# Parallel_CS_V5_repeated.net
KiCad netlist of a schematic drawn in EAGLE
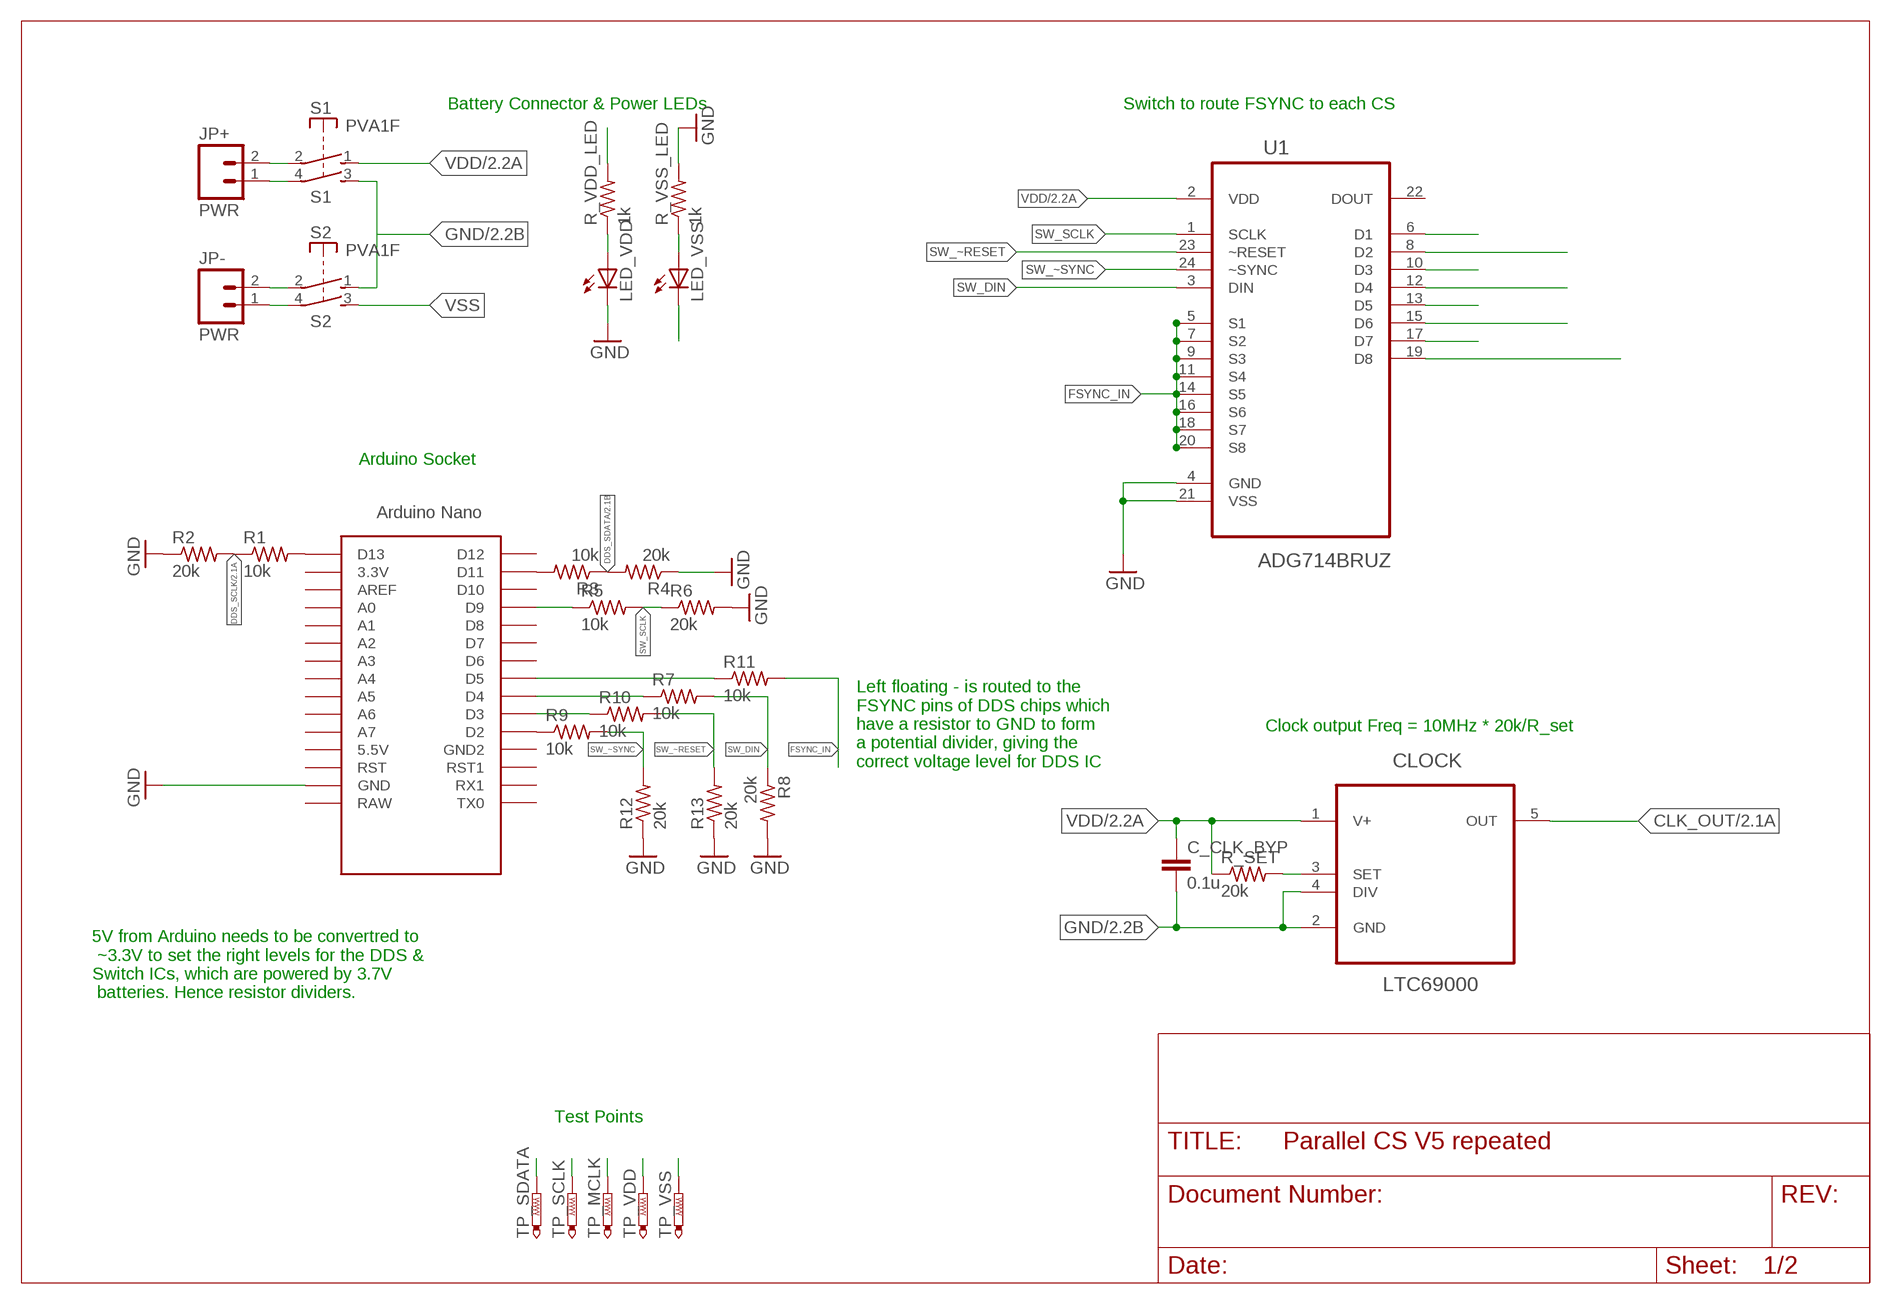
[diagram p0: schematic, sheet 1]
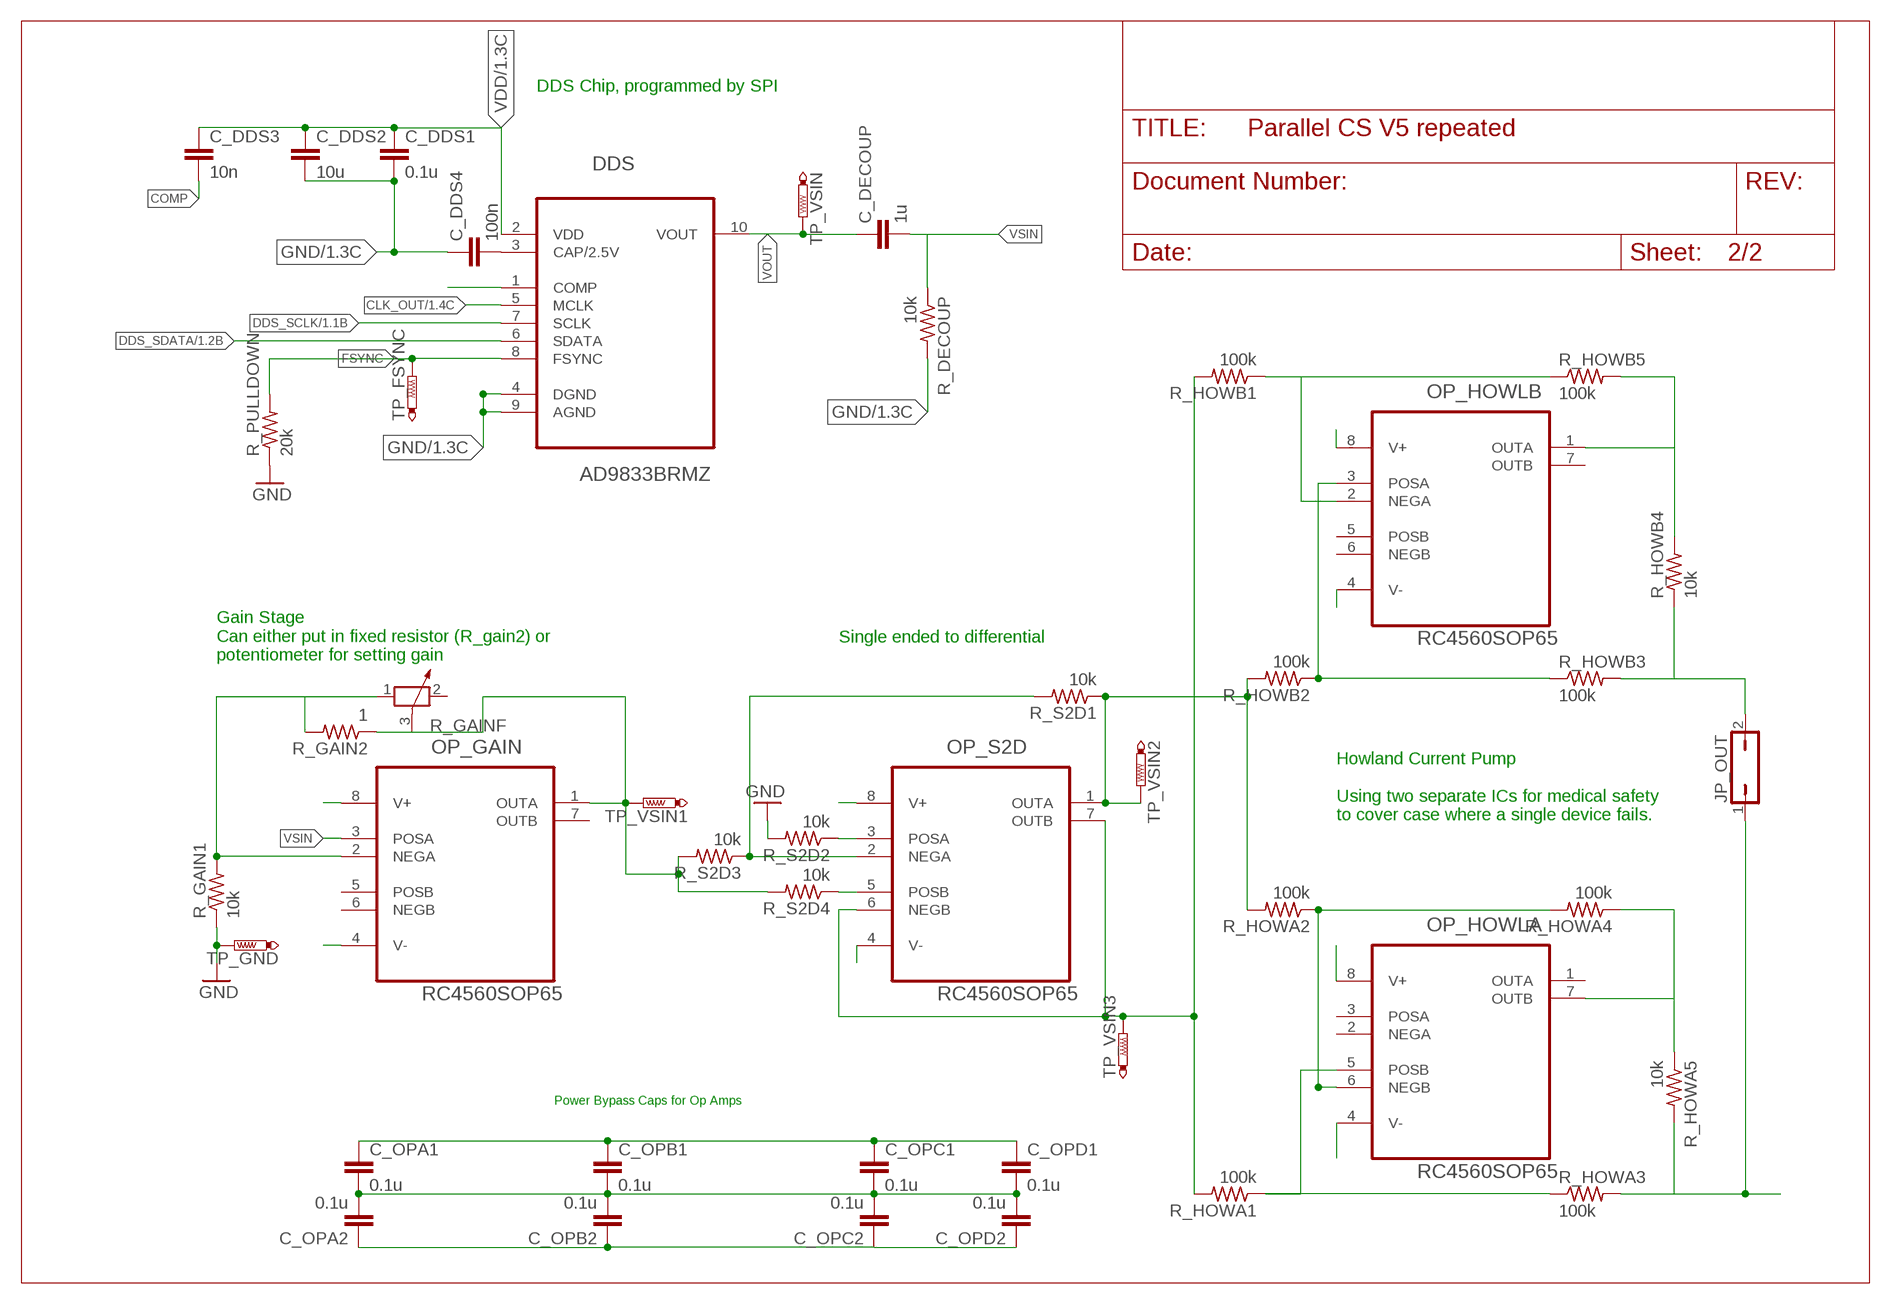
[diagram p1: schematic, sheet 2]

(export (version "E")
  (design (tool "Eeschema 10.0.6"))
  (components
    (comp (ref "CLOCK")
      (value "LTC69000")
      (footprint "eagle-import:SOT23-5L")
      (libsource (lib "eagle-import") (part "LTC69000"))
    )
    (comp (ref "C_CLK_BYP")
      (value "0.1u")
      (footprint "eagle-import:C0805")
      (libsource (lib "eagle-import") (part "C-EUC0805"))
    )
    (comp (ref "JP+")
      (value "PWR")
      (footprint "eagle-import:JST-2-SMD")
      (libsource (lib "eagle-import") (part "M02-JST-2MM-SMT"))
    )
    (comp (ref "JP-")
      (value "PWR")
      (footprint "eagle-import:JST-2-SMD")
      (libsource (lib "eagle-import") (part "M02-JST-2MM-SMT"))
    )
    (comp (ref "LED_VDD")
      (value "LEDSML0805")
      (footprint "eagle-import:SML0805")
      (libsource (lib "eagle-import") (part "LEDSML0805"))
    )
    (comp (ref "LED_VSS")
      (value "LEDSML0805")
      (footprint "eagle-import:SML0805")
      (libsource (lib "eagle-import") (part "LEDSML0805"))
    )
    (comp (ref "R1")
      (value "10k")
      (footprint "eagle-import:R0805")
      (libsource (lib "eagle-import") (part "resistor_R-US_R0805"))
    )
    (comp (ref "R2")
      (value "20k")
      (footprint "eagle-import:R0805")
      (libsource (lib "eagle-import") (part "resistor_R-US_R0805"))
    )
    (comp (ref "R3")
      (value "10k")
      (footprint "eagle-import:R0805")
      (libsource (lib "eagle-import") (part "resistor_R-US_R0805"))
    )
    (comp (ref "R4")
      (value "20k")
      (footprint "eagle-import:R0805")
      (libsource (lib "eagle-import") (part "resistor_R-US_R0805"))
    )
    (comp (ref "R5")
      (value "10k")
      (footprint "eagle-import:R0805")
      (libsource (lib "eagle-import") (part "resistor_R-US_R0805"))
    )
    (comp (ref "R6")
      (value "20k")
      (footprint "eagle-import:R0805")
      (libsource (lib "eagle-import") (part "resistor_R-US_R0805"))
    )
    (comp (ref "R7")
      (value "10k")
      (footprint "eagle-import:R0805")
      (libsource (lib "eagle-import") (part "resistor_R-US_R0805"))
    )
    (comp (ref "R8")
      (value "20k")
      (footprint "eagle-import:R0805")
      (libsource (lib "eagle-import") (part "resistor_R-US_R0805"))
    )
    (comp (ref "R9")
      (value "10k")
      (footprint "eagle-import:R0805")
      (libsource (lib "eagle-import") (part "resistor_R-US_R0805"))
    )
    (comp (ref "R10")
      (value "10k")
      (footprint "eagle-import:R0805")
      (libsource (lib "eagle-import") (part "resistor_R-US_R0805"))
    )
    (comp (ref "R11")
      (value "10k")
      (footprint "eagle-import:R0805")
      (libsource (lib "eagle-import") (part "resistor_R-US_R0805"))
    )
    (comp (ref "R12")
      (value "20k")
      (footprint "eagle-import:R0805")
      (libsource (lib "eagle-import") (part "resistor_R-US_R0805"))
    )
    (comp (ref "R13")
      (value "20k")
      (footprint "eagle-import:R0805")
      (libsource (lib "eagle-import") (part "resistor_R-US_R0805"))
    )
    (comp (ref "R_SET")
      (value "20k")
      (footprint "eagle-import:R0805")
      (libsource (lib "eagle-import") (part "resistor_R-US_R0805"))
    )
    (comp (ref "R_VDD_LED")
      (value "1k")
      (footprint "eagle-import:M0805")
      (libsource (lib "eagle-import") (part "resistor_R-US_M0805"))
    )
    (comp (ref "R_VSS_LED")
      (value "1k")
      (footprint "eagle-import:M0805")
      (libsource (lib "eagle-import") (part "resistor_R-US_M0805"))
    )
    (comp (ref "S1")
      (value "PVA1F")
      (footprint "eagle-import:PVA1F")
      (libsource (lib "eagle-import") (part "PVA1F"))
    )
    (comp (ref "S2")
      (value "PVA1F")
      (footprint "eagle-import:PVA1F")
      (libsource (lib "eagle-import") (part "PVA1F"))
    )
    (comp (ref "TP_MCLK")
      (value "PTR1PAD1-13")
      (footprint "eagle-import:P1-13")
      (libsource (lib "eagle-import") (part "PTR1PAD1-13"))
    )
    (comp (ref "TP_SCLK")
      (value "PTR1PAD1-13")
      (footprint "eagle-import:P1-13")
      (libsource (lib "eagle-import") (part "PTR1PAD1-13"))
    )
    (comp (ref "TP_SDATA")
      (value "PTR1PAD1-13")
      (footprint "eagle-import:P1-13")
      (libsource (lib "eagle-import") (part "PTR1PAD1-13"))
    )
    (comp (ref "TP_VDD")
      (value "PTR1PAD1-13")
      (footprint "eagle-import:P1-13")
      (libsource (lib "eagle-import") (part "PTR1PAD1-13"))
    )
    (comp (ref "TP_VSS")
      (value "PTR1PAD1-13")
      (footprint "eagle-import:P1-13")
      (libsource (lib "eagle-import") (part "PTR1PAD1-13"))
    )
    (comp (ref "U$1")
      (value "NANO")
      (footprint "eagle-import:NANO")
      (libsource (lib "eagle-import") (part "NANO"))
    )
    (comp (ref "U1")
      (value "ADG714BRUZ")
      (footprint "eagle-import:SOP65P640X120-24N")
      (libsource (lib "eagle-import") (part "ADG714BRUZ"))
    )
    (comp (ref "C_DDS1")
      (value "0.1u")
      (footprint "eagle-import:C0805")
      (libsource (lib "eagle-import") (part "C-EUC0805"))
    )
    (comp (ref "C_DDS2")
      (value "10u")
      (footprint "eagle-import:C0805")
      (libsource (lib "eagle-import") (part "C-EUC0805"))
    )
    (comp (ref "C_DDS3")
      (value "10n")
      (footprint "eagle-import:C0805")
      (libsource (lib "eagle-import") (part "C-EUC0805"))
    )
    (comp (ref "C_DDS4")
      (value "100n")
      (footprint "eagle-import:C0805")
      (libsource (lib "eagle-import") (part "C-EUC0805"))
    )
    (comp (ref "C_DECOUP")
      (value "1u")
      (footprint "eagle-import:C0805")
      (libsource (lib "eagle-import") (part "C-EUC0805"))
    )
    (comp (ref "C_OPA1")
      (value "0.1u")
      (footprint "eagle-import:C0805")
      (libsource (lib "eagle-import") (part "C-EUC0805"))
    )
    (comp (ref "C_OPA2")
      (value "0.1u")
      (footprint "eagle-import:C0805")
      (libsource (lib "eagle-import") (part "C-EUC0805"))
    )
    (comp (ref "C_OPB1")
      (value "0.1u")
      (footprint "eagle-import:C0805")
      (libsource (lib "eagle-import") (part "C-EUC0805"))
    )
    (comp (ref "C_OPB2")
      (value "0.1u")
      (footprint "eagle-import:C0805")
      (libsource (lib "eagle-import") (part "C-EUC0805"))
    )
    (comp (ref "C_OPC1")
      (value "0.1u")
      (footprint "eagle-import:C0805")
      (libsource (lib "eagle-import") (part "C-EUC0805"))
    )
    (comp (ref "C_OPC2")
      (value "0.1u")
      (footprint "eagle-import:C0805")
      (libsource (lib "eagle-import") (part "C-EUC0805"))
    )
    (comp (ref "C_OPD1")
      (value "0.1u")
      (footprint "eagle-import:C0805")
      (libsource (lib "eagle-import") (part "C-EUC0805"))
    )
    (comp (ref "C_OPD2")
      (value "0.1u")
      (footprint "eagle-import:C0805")
      (libsource (lib "eagle-import") (part "C-EUC0805"))
    )
    (comp (ref "DDS")
      (value "AD9833BRMZ")
      (footprint "eagle-import:SOP50P490X110-10N")
      (libsource (lib "eagle-import") (part "AD9833BRMZ"))
    )
    (comp (ref "JP_OUT")
      (value "JP1Q")
      (footprint "eagle-import:JP1")
      (libsource (lib "eagle-import") (part "JP1Q"))
    )
    (comp (ref "OP_GAIN")
      (value "RC4560SOP65")
      (footprint "eagle-import:SOP65P490X109-8N")
      (libsource (lib "eagle-import") (part "RC4560SOP65"))
    )
    (comp (ref "OP_HOWLA")
      (value "RC4560SOP65")
      (footprint "eagle-import:SOP65P490X109-8N")
      (libsource (lib "eagle-import") (part "RC4560SOP65"))
    )
    (comp (ref "OP_HOWLB")
      (value "RC4560SOP65")
      (footprint "eagle-import:SOP65P490X109-8N")
      (libsource (lib "eagle-import") (part "RC4560SOP65"))
    )
    (comp (ref "OP_S2D")
      (value "RC4560SOP65")
      (footprint "eagle-import:SOP65P490X109-8N")
      (libsource (lib "eagle-import") (part "RC4560SOP65"))
    )
    (comp (ref "R_DECOUP")
      (value "10k")
      (footprint "eagle-import:R0805")
      (libsource (lib "eagle-import") (part "R-US_R0805"))
    )
    (comp (ref "R_GAIN1")
      (value "10k")
      (footprint "eagle-import:R0805")
      (libsource (lib "eagle-import") (part "R-US_R0805"))
    )
    (comp (ref "R_GAIN2")
      (value "1")
      (footprint "eagle-import:R0805")
      (libsource (lib "eagle-import") (part "R-US_R0805"))
    )
    (comp (ref "R_GAINF")
      (value "POTENTIOMETER_PT-10")
      (footprint "eagle-import:PT-10")
      (libsource (lib "eagle-import") (part "POTENTIOMETER_PT-10"))
    )
    (comp (ref "R_HOWA1")
      (value "100k")
      (footprint "eagle-import:R0805")
      (libsource (lib "eagle-import") (part "R-US_R0805"))
    )
    (comp (ref "R_HOWA2")
      (value "100k")
      (footprint "eagle-import:R0805")
      (libsource (lib "eagle-import") (part "R-US_R0805"))
    )
    (comp (ref "R_HOWA3")
      (value "100k")
      (footprint "eagle-import:R0805")
      (libsource (lib "eagle-import") (part "R-US_R0805"))
    )
    (comp (ref "R_HOWA4")
      (value "100k")
      (footprint "eagle-import:R0805")
      (libsource (lib "eagle-import") (part "R-US_R0805"))
    )
    (comp (ref "R_HOWA5")
      (value "10k")
      (footprint "eagle-import:R0805")
      (libsource (lib "eagle-import") (part "R-US_R0805"))
    )
    (comp (ref "R_HOWB1")
      (value "100k")
      (footprint "eagle-import:R0805")
      (libsource (lib "eagle-import") (part "R-US_R0805"))
    )
    (comp (ref "R_HOWB2")
      (value "100k")
      (footprint "eagle-import:R0805")
      (libsource (lib "eagle-import") (part "R-US_R0805"))
    )
    (comp (ref "R_HOWB3")
      (value "100k")
      (footprint "eagle-import:R0805")
      (libsource (lib "eagle-import") (part "R-US_R0805"))
    )
    (comp (ref "R_HOWB4")
      (value "10k")
      (footprint "eagle-import:R0805")
      (libsource (lib "eagle-import") (part "R-US_R0805"))
    )
    (comp (ref "R_HOWB5")
      (value "100k")
      (footprint "eagle-import:R0805")
      (libsource (lib "eagle-import") (part "R-US_R0805"))
    )
    (comp (ref "R_PULLDOWN")
      (value "20k")
      (footprint "eagle-import:R0805")
      (libsource (lib "eagle-import") (part "R-US_R0805"))
    )
    (comp (ref "R_S2D1")
      (value "10k")
      (footprint "eagle-import:R0805")
      (libsource (lib "eagle-import") (part "R-US_R0805"))
    )
    (comp (ref "R_S2D2")
      (value "10k")
      (footprint "eagle-import:R0805")
      (libsource (lib "eagle-import") (part "R-US_R0805"))
    )
    (comp (ref "R_S2D3")
      (value "10k")
      (footprint "eagle-import:R0805")
      (libsource (lib "eagle-import") (part "R-US_R0805"))
    )
    (comp (ref "R_S2D4")
      (value "10k")
      (footprint "eagle-import:R0805")
      (libsource (lib "eagle-import") (part "R-US_R0805"))
    )
    (comp (ref "TP_FSYNC")
      (value "PTR1PAD1-13")
      (footprint "eagle-import:P1-13")
      (libsource (lib "eagle-import") (part "PTR1PAD1-13"))
    )
    (comp (ref "TP_GND")
      (value "PTR1PAD1-13")
      (footprint "eagle-import:P1-13")
      (libsource (lib "eagle-import") (part "PTR1PAD1-13"))
    )
    (comp (ref "TP_VSIN")
      (value "PTR1PAD1-13")
      (footprint "eagle-import:P1-13")
      (libsource (lib "eagle-import") (part "PTR1PAD1-13"))
    )
    (comp (ref "TP_VSIN1")
      (value "PTR1PAD1-13")
      (footprint "eagle-import:P1-13")
      (libsource (lib "eagle-import") (part "PTR1PAD1-13"))
    )
    (comp (ref "TP_VSIN2")
      (value "PTR1PAD1-13")
      (footprint "eagle-import:P1-13")
      (libsource (lib "eagle-import") (part "PTR1PAD1-13"))
    )
    (comp (ref "TP_VSIN3")
      (value "PTR1PAD1-13")
      (footprint "eagle-import:P1-13")
      (libsource (lib "eagle-import") (part "PTR1PAD1-13"))
    )
  )
  (nets
    (net (code "1") (name "CLK_OUT") (class "Default")
      (node (ref "CLOCK") (pin "5") (pinfunction "OUT_5") (pintype "output"))
      (node (ref "DDS") (pin "5") (pinfunction "MCLK_5") (pintype "input"))
      (node (ref "TP_MCLK") (pin "TP") (pinfunction "TP_TP") (pintype "input"))
    )
    (net (code "2") (name "COMP") (class "Default")
      (node (ref "C_DDS3") (pin "2") (pinfunction "2_2") (pintype "passive"))
      (node (ref "DDS") (pin "1") (pinfunction "COMP_1") (pintype "passive"))
    )
    (net (code "3") (name "DDS_SCLK") (class "Default")
      (node (ref "DDS") (pin "7") (pinfunction "SCLK_7") (pintype "input"))
      (node (ref "R1") (pin "1") (pinfunction "1_1") (pintype "passive"))
      (node (ref "R2") (pin "2") (pinfunction "2_2") (pintype "passive"))
      (node (ref "TP_SCLK") (pin "TP") (pinfunction "TP_TP") (pintype "input"))
    )
    (net (code "4") (name "DDS_SDATA") (class "Default")
      (node (ref "DDS") (pin "6") (pinfunction "SDATA_6") (pintype "input"))
      (node (ref "R3") (pin "1") (pinfunction "1_1") (pintype "passive"))
      (node (ref "R4") (pin "2") (pinfunction "2_2") (pintype "passive"))
      (node (ref "TP_SDATA") (pin "TP") (pinfunction "TP_TP") (pintype "input"))
    )
    (net (code "5") (name "FSYNC") (class "Default")
      (node (ref "DDS") (pin "8") (pinfunction "FSYNC_8") (pintype "input"))
      (node (ref "R_PULLDOWN") (pin "2") (pinfunction "2_2") (pintype "passive"))
      (node (ref "TP_FSYNC") (pin "TP") (pinfunction "TP_TP") (pintype "input"))
    )
    (net (code "6") (name "FSYNC_IN") (class "Default")
      (node (ref "R11") (pin "2") (pinfunction "2_2") (pintype "passive"))
      (node (ref "U1") (pin "11") (pinfunction "S4_11") (pintype "bidirectional"))
      (node (ref "U1") (pin "14") (pinfunction "S5_14") (pintype "bidirectional"))
      (node (ref "U1") (pin "16") (pinfunction "S6_16") (pintype "bidirectional"))
      (node (ref "U1") (pin "18") (pinfunction "S7_18") (pintype "bidirectional"))
      (node (ref "U1") (pin "20") (pinfunction "S8_20") (pintype "bidirectional"))
      (node (ref "U1") (pin "5") (pinfunction "S1_5") (pintype "bidirectional"))
      (node (ref "U1") (pin "7") (pinfunction "S2_7") (pintype "bidirectional"))
      (node (ref "U1") (pin "9") (pinfunction "S3_9") (pintype "bidirectional"))
    )
    (net (code "7") (name "GND") (class "Default")
      (node (ref "CLOCK") (pin "2") (pinfunction "GND_2") (pintype "passive"))
      (node (ref "CLOCK") (pin "4") (pinfunction "DIV_4") (pintype "input"))
      (node (ref "C_CLK_BYP") (pin "2") (pinfunction "2_2") (pintype "passive"))
      (node (ref "C_DDS1") (pin "2") (pinfunction "2_2") (pintype "passive"))
      (node (ref "C_DDS2") (pin "2") (pinfunction "2_2") (pintype "passive"))
      (node (ref "C_DDS4") (pin "1") (pinfunction "1_1") (pintype "passive"))
      (node (ref "C_OPA1") (pin "2") (pinfunction "2_2") (pintype "passive"))
      (node (ref "C_OPA2") (pin "2") (pinfunction "2_2") (pintype "passive"))
      (node (ref "C_OPB1") (pin "2") (pinfunction "2_2") (pintype "passive"))
      (node (ref "C_OPB2") (pin "2") (pinfunction "2_2") (pintype "passive"))
      (node (ref "C_OPC1") (pin "2") (pinfunction "2_2") (pintype "passive"))
      (node (ref "C_OPC2") (pin "2") (pinfunction "2_2") (pintype "passive"))
      (node (ref "C_OPD1") (pin "2") (pinfunction "2_2") (pintype "passive"))
      (node (ref "C_OPD2") (pin "2") (pinfunction "2_2") (pintype "passive"))
      (node (ref "DDS") (pin "4") (pinfunction "DGND_4") (pintype "passive"))
      (node (ref "DDS") (pin "9") (pinfunction "AGND_9") (pintype "passive"))
      (node (ref "LED_VDD") (pin "C") (pinfunction "C_C") (pintype "passive"))
      (node (ref "R12") (pin "1") (pinfunction "1_1") (pintype "passive"))
      (node (ref "R13") (pin "1") (pinfunction "1_1") (pintype "passive"))
      (node (ref "R2") (pin "1") (pinfunction "1_1") (pintype "passive"))
      (node (ref "R4") (pin "1") (pinfunction "1_1") (pintype "passive"))
      (node (ref "R6") (pin "2") (pinfunction "2_2") (pintype "passive"))
      (node (ref "R8") (pin "2") (pinfunction "2_2") (pintype "passive"))
      (node (ref "R_DECOUP") (pin "2") (pinfunction "2_2") (pintype "passive"))
      (node (ref "R_GAIN1") (pin "1") (pinfunction "1_1") (pintype "passive"))
      (node (ref "R_PULLDOWN") (pin "1") (pinfunction "1_1") (pintype "passive"))
      (node (ref "R_S2D2") (pin "2") (pinfunction "2_2") (pintype "passive"))
      (node (ref "R_VSS_LED") (pin "2") (pinfunction "2_2") (pintype "passive"))
      (node (ref "S1") (pin "3") (pinfunction "S_3") (pintype "passive"))
      (node (ref "S2") (pin "1") (pinfunction "S_1") (pintype "passive"))
      (node (ref "TP_GND") (pin "TP") (pinfunction "TP_TP") (pintype "input"))
      (node (ref "U$1") (pin "GND") (pinfunction "GND_GND") (pintype "bidirectional"))
      (node (ref "U1") (pin "21") (pinfunction "VSS_21") (pintype "power_in"))
      (node (ref "U1") (pin "4") (pinfunction "GND_4") (pintype "passive"))
    )
    (net (code "8") (name "Net-(CLOCK-SET)") (class "Default")
      (node (ref "CLOCK") (pin "3") (pinfunction "SET_3") (pintype "input"))
      (node (ref "R_SET") (pin "2") (pinfunction "2_2") (pintype "passive"))
    )
    (net (code "9") (name "Net-(DDS-CAP{slash}2.5V)") (class "Default")
      (node (ref "C_DDS4") (pin "2") (pinfunction "2_2") (pintype "passive"))
      (node (ref "DDS") (pin "3") (pinfunction "CAP/2.5V_3") (pintype "passive"))
    )
    (net (code "10") (name "Net-(JP_OUT-Pad1)") (class "Default")
      (node (ref "JP_OUT") (pin "1") (pinfunction "1_1") (pintype "passive"))
      (node (ref "R_HOWA3") (pin "2") (pinfunction "2_2") (pintype "passive"))
      (node (ref "R_HOWA5") (pin "2") (pinfunction "2_2") (pintype "passive"))
    )
    (net (code "11") (name "Net-(JP_OUT-Pad2)") (class "Default")
      (node (ref "JP_OUT") (pin "2") (pinfunction "2_2") (pintype "passive"))
      (node (ref "R_HOWB3") (pin "2") (pinfunction "2_2") (pintype "passive"))
      (node (ref "R_HOWB4") (pin "1") (pinfunction "1_1") (pintype "passive"))
    )
    (net (code "12") (name "Net-(LED_VDD-PadA)") (class "Default")
      (node (ref "LED_VDD") (pin "A") (pinfunction "A_A") (pintype "passive"))
      (node (ref "R_VDD_LED") (pin "1") (pinfunction "1_1") (pintype "passive"))
    )
    (net (code "13") (name "Net-(LED_VSS-PadA)") (class "Default")
      (node (ref "LED_VSS") (pin "A") (pinfunction "A_A") (pintype "passive"))
      (node (ref "R_VSS_LED") (pin "1") (pinfunction "1_1") (pintype "passive"))
    )
    (net (code "14") (name "Net-(OP_GAIN-NEGA)") (class "Default")
      (node (ref "OP_GAIN") (pin "2") (pinfunction "NEGA_2") (pintype "input"))
      (node (ref "R_GAIN1") (pin "2") (pinfunction "2_2") (pintype "passive"))
      (node (ref "R_GAIN2") (pin "2") (pinfunction "2_2") (pintype "passive"))
      (node (ref "R_GAINF") (pin "1") (pinfunction "1_1") (pintype "passive"))
    )
    (net (code "15") (name "Net-(OP_GAIN-OUTA)") (class "Default")
      (node (ref "OP_GAIN") (pin "1") (pinfunction "OUTA_1") (pintype "output"))
      (node (ref "R_GAIN2") (pin "1") (pinfunction "1_1") (pintype "passive"))
      (node (ref "R_GAINF") (pin "3") (pinfunction "3_3") (pintype "passive"))
      (node (ref "R_S2D3") (pin "2") (pinfunction "2_2") (pintype "passive"))
      (node (ref "R_S2D4") (pin "2") (pinfunction "2_2") (pintype "passive"))
      (node (ref "TP_VSIN1") (pin "TP") (pinfunction "TP_TP") (pintype "input"))
    )
    (net (code "16") (name "Net-(OP_HOWLA-NEGB)") (class "Default")
      (node (ref "OP_HOWLA") (pin "6") (pinfunction "NEGB_6") (pintype "input"))
      (node (ref "R_HOWA2") (pin "1") (pinfunction "1_1") (pintype "passive"))
      (node (ref "R_HOWA4") (pin "2") (pinfunction "2_2") (pintype "passive"))
    )
    (net (code "17") (name "Net-(OP_HOWLA-OUTB)") (class "Default")
      (node (ref "OP_HOWLA") (pin "7") (pinfunction "OUTB_7") (pintype "output"))
      (node (ref "R_HOWA4") (pin "1") (pinfunction "1_1") (pintype "passive"))
      (node (ref "R_HOWA5") (pin "1") (pinfunction "1_1") (pintype "passive"))
    )
    (net (code "18") (name "Net-(OP_HOWLA-POSB)") (class "Default")
      (node (ref "OP_HOWLA") (pin "5") (pinfunction "POSB_5") (pintype "input"))
      (node (ref "R_HOWA1") (pin "1") (pinfunction "1_1") (pintype "passive"))
      (node (ref "R_HOWA3") (pin "1") (pinfunction "1_1") (pintype "passive"))
    )
    (net (code "19") (name "Net-(OP_HOWLB-NEGA)") (class "Default")
      (node (ref "OP_HOWLB") (pin "2") (pinfunction "NEGA_2") (pintype "input"))
      (node (ref "R_HOWB1") (pin "1") (pinfunction "1_1") (pintype "passive"))
      (node (ref "R_HOWB5") (pin "1") (pinfunction "1_1") (pintype "passive"))
    )
    (net (code "20") (name "Net-(OP_HOWLB-OUTA)") (class "Default")
      (node (ref "OP_HOWLB") (pin "1") (pinfunction "OUTA_1") (pintype "output"))
      (node (ref "R_HOWB4") (pin "2") (pinfunction "2_2") (pintype "passive"))
      (node (ref "R_HOWB5") (pin "2") (pinfunction "2_2") (pintype "passive"))
    )
    (net (code "21") (name "Net-(OP_HOWLB-POSA)") (class "Default")
      (node (ref "OP_HOWLB") (pin "3") (pinfunction "POSA_3") (pintype "input"))
      (node (ref "R_HOWB2") (pin "1") (pinfunction "1_1") (pintype "passive"))
      (node (ref "R_HOWB3") (pin "1") (pinfunction "1_1") (pintype "passive"))
    )
    (net (code "22") (name "Net-(OP_S2D-NEGA)") (class "Default")
      (node (ref "OP_S2D") (pin "2") (pinfunction "NEGA_2") (pintype "input"))
      (node (ref "R_S2D1") (pin "2") (pinfunction "2_2") (pintype "passive"))
      (node (ref "R_S2D3") (pin "1") (pinfunction "1_1") (pintype "passive"))
    )
    (net (code "23") (name "Net-(OP_S2D-NEGB)") (class "Default")
      (node (ref "OP_S2D") (pin "6") (pinfunction "NEGB_6") (pintype "input"))
      (node (ref "OP_S2D") (pin "7") (pinfunction "OUTB_7") (pintype "output"))
      (node (ref "R_HOWA1") (pin "2") (pinfunction "2_2") (pintype "passive"))
      (node (ref "R_HOWB1") (pin "2") (pinfunction "2_2") (pintype "passive"))
      (node (ref "TP_VSIN3") (pin "TP") (pinfunction "TP_TP") (pintype "input"))
    )
    (net (code "24") (name "Net-(OP_S2D-OUTA)") (class "Default")
      (node (ref "OP_S2D") (pin "1") (pinfunction "OUTA_1") (pintype "output"))
      (node (ref "R_HOWA2") (pin "2") (pinfunction "2_2") (pintype "passive"))
      (node (ref "R_HOWB2") (pin "2") (pinfunction "2_2") (pintype "passive"))
      (node (ref "R_S2D1") (pin "1") (pinfunction "1_1") (pintype "passive"))
      (node (ref "TP_VSIN2") (pin "TP") (pinfunction "TP_TP") (pintype "input"))
    )
    (net (code "25") (name "Net-(OP_S2D-POSA)") (class "Default")
      (node (ref "OP_S2D") (pin "3") (pinfunction "POSA_3") (pintype "input"))
      (node (ref "R_S2D2") (pin "1") (pinfunction "1_1") (pintype "passive"))
    )
    (net (code "26") (name "Net-(OP_S2D-POSB)") (class "Default")
      (node (ref "OP_S2D") (pin "5") (pinfunction "POSB_5") (pintype "input"))
      (node (ref "R_S2D4") (pin "1") (pinfunction "1_1") (pintype "passive"))
    )
    (net (code "27") (name "Net-(R1-Pad2)") (class "Default")
      (node (ref "R1") (pin "2") (pinfunction "2_2") (pintype "passive"))
      (node (ref "U$1") (pin "D13") (pinfunction "D13_D13") (pintype "bidirectional"))
    )
    (net (code "28") (name "Net-(R3-Pad2)") (class "Default")
      (node (ref "R3") (pin "2") (pinfunction "2_2") (pintype "passive"))
      (node (ref "U$1") (pin "D11") (pinfunction "D11_D11") (pintype "bidirectional"))
    )
    (net (code "29") (name "Net-(R5-Pad1)") (class "Default")
      (node (ref "R5") (pin "1") (pinfunction "1_1") (pintype "passive"))
      (node (ref "U$1") (pin "D9") (pinfunction "D9_D9") (pintype "bidirectional"))
    )
    (net (code "30") (name "Net-(R7-Pad1)") (class "Default")
      (node (ref "R7") (pin "1") (pinfunction "1_1") (pintype "passive"))
      (node (ref "U$1") (pin "D4") (pinfunction "D4_D4") (pintype "bidirectional"))
    )
    (net (code "31") (name "Net-(R9-Pad1)") (class "Default")
      (node (ref "R9") (pin "1") (pinfunction "1_1") (pintype "passive"))
      (node (ref "U$1") (pin "D2") (pinfunction "D2_D2") (pintype "bidirectional"))
    )
    (net (code "32") (name "Net-(R10-Pad1)") (class "Default")
      (node (ref "R10") (pin "1") (pinfunction "1_1") (pintype "passive"))
      (node (ref "U$1") (pin "D3") (pinfunction "D3_D3") (pintype "bidirectional"))
    )
    (net (code "33") (name "Net-(R11-Pad1)") (class "Default")
      (node (ref "R11") (pin "1") (pinfunction "1_1") (pintype "passive"))
      (node (ref "U$1") (pin "D5") (pinfunction "D5_D5") (pintype "bidirectional"))
    )
    (net (code "34") (name "Net-(S1A-P)") (class "Default")
      (node (ref "JP+") (pin "2") (pinfunction "2_2") (pintype "passive"))
      (node (ref "S1") (pin "2") (pinfunction "P_2") (pintype "passive"))
    )
    (net (code "35") (name "Net-(S1B-P)") (class "Default")
      (node (ref "JP+") (pin "1") (pinfunction "1_1") (pintype "passive"))
      (node (ref "S1") (pin "4") (pinfunction "P_4") (pintype "passive"))
    )
    (net (code "36") (name "Net-(S2A-P)") (class "Default")
      (node (ref "JP-") (pin "2") (pinfunction "2_2") (pintype "passive"))
      (node (ref "S2") (pin "2") (pinfunction "P_2") (pintype "passive"))
    )
    (net (code "37") (name "Net-(S2B-P)") (class "Default")
      (node (ref "JP-") (pin "1") (pinfunction "1_1") (pintype "passive"))
      (node (ref "S2") (pin "4") (pinfunction "P_4") (pintype "passive"))
    )
    (net (code "38") (name "SW_DIN") (class "Default")
      (node (ref "R7") (pin "2") (pinfunction "2_2") (pintype "passive"))
      (node (ref "R8") (pin "1") (pinfunction "1_1") (pintype "passive"))
      (node (ref "U1") (pin "3") (pinfunction "DIN_3") (pintype "input"))
    )
    (net (code "39") (name "SW_SCLK") (class "Default")
      (node (ref "R5") (pin "2") (pinfunction "2_2") (pintype "passive"))
      (node (ref "R6") (pin "1") (pinfunction "1_1") (pintype "passive"))
      (node (ref "U1") (pin "1") (pinfunction "SCLK_1") (pintype "input"))
    )
    (net (code "40") (name "SW_~{RESET}") (class "Default")
      (node (ref "R10") (pin "2") (pinfunction "2_2") (pintype "passive"))
      (node (ref "R13") (pin "2") (pinfunction "2_2") (pintype "passive"))
      (node (ref "U1") (pin "23") (pinfunction "~{RESET}_23") (pintype "input"))
    )
    (net (code "41") (name "SW_~{SYNC}") (class "Default")
      (node (ref "R12") (pin "2") (pinfunction "2_2") (pintype "passive"))
      (node (ref "R9") (pin "2") (pinfunction "2_2") (pintype "passive"))
      (node (ref "U1") (pin "24") (pinfunction "~{SYNC}_24") (pintype "input"))
    )
    (net (code "42") (name "VDD") (class "Default")
      (node (ref "CLOCK") (pin "1") (pinfunction "V+_1") (pintype "power_in"))
      (node (ref "C_CLK_BYP") (pin "1") (pinfunction "1_1") (pintype "passive"))
      (node (ref "C_DDS1") (pin "1") (pinfunction "1_1") (pintype "passive"))
      (node (ref "C_DDS2") (pin "1") (pinfunction "1_1") (pintype "passive"))
      (node (ref "C_DDS3") (pin "1") (pinfunction "1_1") (pintype "passive"))
      (node (ref "C_OPA1") (pin "1") (pinfunction "1_1") (pintype "passive"))
      (node (ref "C_OPB1") (pin "1") (pinfunction "1_1") (pintype "passive"))
      (node (ref "C_OPC1") (pin "1") (pinfunction "1_1") (pintype "passive"))
      (node (ref "C_OPD1") (pin "1") (pinfunction "1_1") (pintype "passive"))
      (node (ref "DDS") (pin "2") (pinfunction "VDD_2") (pintype "power_in"))
      (node (ref "OP_GAIN") (pin "8") (pinfunction "V+_8") (pintype "power_in"))
      (node (ref "OP_HOWLA") (pin "8") (pinfunction "V+_8") (pintype "power_in"))
      (node (ref "OP_HOWLB") (pin "8") (pinfunction "V+_8") (pintype "power_in"))
      (node (ref "OP_S2D") (pin "8") (pinfunction "V+_8") (pintype "power_in"))
      (node (ref "R_SET") (pin "1") (pinfunction "1_1") (pintype "passive"))
      (node (ref "R_VDD_LED") (pin "2") (pinfunction "2_2") (pintype "passive"))
      (node (ref "S1") (pin "1") (pinfunction "S_1") (pintype "passive"))
      (node (ref "TP_VDD") (pin "TP") (pinfunction "TP_TP") (pintype "input"))
      (node (ref "U1") (pin "2") (pinfunction "VDD_2") (pintype "power_in"))
    )
    (net (code "43") (name "VOUT") (class "Default")
      (node (ref "C_DECOUP") (pin "1") (pinfunction "1_1") (pintype "passive"))
      (node (ref "DDS") (pin "10") (pinfunction "VOUT_10") (pintype "output"))
      (node (ref "TP_VSIN") (pin "TP") (pinfunction "TP_TP") (pintype "input"))
    )
    (net (code "44") (name "VSIN") (class "Default")
      (node (ref "C_DECOUP") (pin "2") (pinfunction "2_2") (pintype "passive"))
      (node (ref "OP_GAIN") (pin "3") (pinfunction "POSA_3") (pintype "input"))
      (node (ref "R_DECOUP") (pin "1") (pinfunction "1_1") (pintype "passive"))
    )
    (net (code "45") (name "VSS") (class "Default")
      (node (ref "C_OPA2") (pin "1") (pinfunction "1_1") (pintype "passive"))
      (node (ref "C_OPB2") (pin "1") (pinfunction "1_1") (pintype "passive"))
      (node (ref "C_OPC2") (pin "1") (pinfunction "1_1") (pintype "passive"))
      (node (ref "C_OPD2") (pin "1") (pinfunction "1_1") (pintype "passive"))
      (node (ref "LED_VSS") (pin "C") (pinfunction "C_C") (pintype "passive"))
      (node (ref "OP_GAIN") (pin "4") (pinfunction "V-_4") (pintype "power_in"))
      (node (ref "OP_HOWLA") (pin "4") (pinfunction "V-_4") (pintype "power_in"))
      (node (ref "OP_HOWLB") (pin "4") (pinfunction "V-_4") (pintype "power_in"))
      (node (ref "OP_S2D") (pin "4") (pinfunction "V-_4") (pintype "power_in"))
      (node (ref "S2") (pin "3") (pinfunction "S_3") (pintype "passive"))
      (node (ref "TP_VSS") (pin "TP") (pinfunction "TP_TP") (pintype "input"))
    )
    (net (code "46") (name "unconnected-(OP_GAIN-NEGB-Pad6)") (class "Default")
      (node (ref "OP_GAIN") (pin "6") (pinfunction "NEGB_6") (pintype "input"))
    )
    (net (code "47") (name "unconnected-(OP_GAIN-OUTB-Pad7)") (class "Default")
      (node (ref "OP_GAIN") (pin "7") (pinfunction "OUTB_7") (pintype "output"))
    )
    (net (code "48") (name "unconnected-(OP_GAIN-POSB-Pad5)") (class "Default")
      (node (ref "OP_GAIN") (pin "5") (pinfunction "POSB_5") (pintype "input"))
    )
    (net (code "49") (name "unconnected-(OP_HOWLA-NEGA-Pad2)") (class "Default")
      (node (ref "OP_HOWLA") (pin "2") (pinfunction "NEGA_2") (pintype "input"))
    )
    (net (code "50") (name "unconnected-(OP_HOWLA-OUTA-Pad1)") (class "Default")
      (node (ref "OP_HOWLA") (pin "1") (pinfunction "OUTA_1") (pintype "output"))
    )
    (net (code "51") (name "unconnected-(OP_HOWLA-POSA-Pad3)") (class "Default")
      (node (ref "OP_HOWLA") (pin "3") (pinfunction "POSA_3") (pintype "input"))
    )
    (net (code "52") (name "unconnected-(OP_HOWLB-NEGB-Pad6)") (class "Default")
      (node (ref "OP_HOWLB") (pin "6") (pinfunction "NEGB_6") (pintype "input"))
    )
    (net (code "53") (name "unconnected-(OP_HOWLB-OUTB-Pad7)") (class "Default")
      (node (ref "OP_HOWLB") (pin "7") (pinfunction "OUTB_7") (pintype "output"))
    )
    (net (code "54") (name "unconnected-(OP_HOWLB-POSB-Pad5)") (class "Default")
      (node (ref "OP_HOWLB") (pin "5") (pinfunction "POSB_5") (pintype "input"))
    )
    (net (code "55") (name "unconnected-(R_GAINF-Pad2)") (class "Default")
      (node (ref "R_GAINF") (pin "2") (pinfunction "2_2") (pintype "passive"))
    )
    (net (code "56") (name "unconnected-(U$1-5.5V-Pad5V)") (class "Default")
      (node (ref "U$1") (pin "5V") (pinfunction "5.5V_5V") (pintype "bidirectional"))
    )
    (net (code "57") (name "unconnected-(U$1-GND2-PadGND1)") (class "Default")
      (node (ref "U$1") (pin "GND1") (pinfunction "GND2_GND1") (pintype "bidirectional"))
    )
    (net (code "58") (name "unconnected-(U$1-Pad3.3V)") (class "Default")
      (node (ref "U$1") (pin "3.3V") (pinfunction "3.3V_3.3V") (pintype "bidirectional"))
    )
    (net (code "59") (name "unconnected-(U$1-PadA0)") (class "Default")
      (node (ref "U$1") (pin "A0") (pinfunction "A0_A0") (pintype "bidirectional"))
    )
    (net (code "60") (name "unconnected-(U$1-PadA1)") (class "Default")
      (node (ref "U$1") (pin "A1") (pinfunction "A1_A1") (pintype "bidirectional"))
    )
    (net (code "61") (name "unconnected-(U$1-PadA2)") (class "Default")
      (node (ref "U$1") (pin "A2") (pinfunction "A2_A2") (pintype "bidirectional"))
    )
    (net (code "62") (name "unconnected-(U$1-PadA3)") (class "Default")
      (node (ref "U$1") (pin "A3") (pinfunction "A3_A3") (pintype "bidirectional"))
    )
    (net (code "63") (name "unconnected-(U$1-PadA4)") (class "Default")
      (node (ref "U$1") (pin "A4") (pinfunction "A4_A4") (pintype "bidirectional"))
    )
    (net (code "64") (name "unconnected-(U$1-PadA5)") (class "Default")
      (node (ref "U$1") (pin "A5") (pinfunction "A5_A5") (pintype "bidirectional"))
    )
    (net (code "65") (name "unconnected-(U$1-PadA6)") (class "Default")
      (node (ref "U$1") (pin "A6") (pinfunction "A6_A6") (pintype "bidirectional"))
    )
    (net (code "66") (name "unconnected-(U$1-PadA7)") (class "Default")
      (node (ref "U$1") (pin "A7") (pinfunction "A7_A7") (pintype "bidirectional"))
    )
    (net (code "67") (name "unconnected-(U$1-PadAREF)") (class "Default")
      (node (ref "U$1") (pin "AREF") (pinfunction "AREF_AREF") (pintype "bidirectional"))
    )
    (net (code "68") (name "unconnected-(U$1-PadD6)") (class "Default")
      (node (ref "U$1") (pin "D6") (pinfunction "D6_D6") (pintype "bidirectional"))
    )
    (net (code "69") (name "unconnected-(U$1-PadD7)") (class "Default")
      (node (ref "U$1") (pin "D7") (pinfunction "D7_D7") (pintype "bidirectional"))
    )
    (net (code "70") (name "unconnected-(U$1-PadD8)") (class "Default")
      (node (ref "U$1") (pin "D8") (pinfunction "D8_D8") (pintype "bidirectional"))
    )
    (net (code "71") (name "unconnected-(U$1-PadD10)") (class "Default")
      (node (ref "U$1") (pin "D10") (pinfunction "D10_D10") (pintype "bidirectional"))
    )
    (net (code "72") (name "unconnected-(U$1-PadD12)") (class "Default")
      (node (ref "U$1") (pin "D12") (pinfunction "D12_D12") (pintype "bidirectional"))
    )
    (net (code "73") (name "unconnected-(U$1-PadICSP1)") (class "Default")
      (node (ref "U$1") (pin "ICSP1") (pinfunction "ICSP1_ICSP1") (pintype "bidirectional"))
    )
    (net (code "74") (name "unconnected-(U$1-PadICSP2)") (class "Default")
      (node (ref "U$1") (pin "ICSP2") (pinfunction "ICSP2_ICSP2") (pintype "bidirectional"))
    )
    (net (code "75") (name "unconnected-(U$1-PadICSP3)") (class "Default")
      (node (ref "U$1") (pin "ICSP3") (pinfunction "ICSP3_ICSP3") (pintype "bidirectional"))
    )
    (net (code "76") (name "unconnected-(U$1-PadICSP4)") (class "Default")
      (node (ref "U$1") (pin "ICSP4") (pinfunction "ICSP4_ICSP4") (pintype "bidirectional"))
    )
    (net (code "77") (name "unconnected-(U$1-PadICSP5)") (class "Default")
      (node (ref "U$1") (pin "ICSP5") (pinfunction "ICSP5_ICSP5") (pintype "bidirectional"))
    )
    (net (code "78") (name "unconnected-(U$1-PadICSP6)") (class "Default")
      (node (ref "U$1") (pin "ICSP6") (pinfunction "ICSP6_ICSP6") (pintype "bidirectional"))
    )
    (net (code "79") (name "unconnected-(U$1-PadRAW)") (class "Default")
      (node (ref "U$1") (pin "RAW") (pinfunction "RAW_RAW") (pintype "bidirectional"))
    )
    (net (code "80") (name "unconnected-(U$1-PadRST)") (class "Default")
      (node (ref "U$1") (pin "RST") (pinfunction "RST_RST") (pintype "bidirectional"))
    )
    (net (code "81") (name "unconnected-(U$1-PadRST1)") (class "Default")
      (node (ref "U$1") (pin "RST1") (pinfunction "RST1_RST1") (pintype "bidirectional"))
    )
    (net (code "82") (name "unconnected-(U$1-PadRX1)") (class "Default")
      (node (ref "U$1") (pin "RX1") (pinfunction "RX1_RX1") (pintype "bidirectional"))
    )
    (net (code "83") (name "unconnected-(U$1-PadTX0)") (class "Default")
      (node (ref "U$1") (pin "TX0") (pinfunction "TX0_TX0") (pintype "bidirectional"))
    )
    (net (code "84") (name "unconnected-(U1-D1-Pad6)") (class "Default")
      (node (ref "U1") (pin "6") (pinfunction "D1_6") (pintype "bidirectional"))
    )
    (net (code "85") (name "unconnected-(U1-D2-Pad8)") (class "Default")
      (node (ref "U1") (pin "8") (pinfunction "D2_8") (pintype "bidirectional"))
    )
    (net (code "86") (name "unconnected-(U1-D3-Pad10)") (class "Default")
      (node (ref "U1") (pin "10") (pinfunction "D3_10") (pintype "bidirectional"))
    )
    (net (code "87") (name "unconnected-(U1-D4-Pad12)") (class "Default")
      (node (ref "U1") (pin "12") (pinfunction "D4_12") (pintype "bidirectional"))
    )
    (net (code "88") (name "unconnected-(U1-D5-Pad13)") (class "Default")
      (node (ref "U1") (pin "13") (pinfunction "D5_13") (pintype "bidirectional"))
    )
    (net (code "89") (name "unconnected-(U1-D6-Pad15)") (class "Default")
      (node (ref "U1") (pin "15") (pinfunction "D6_15") (pintype "bidirectional"))
    )
    (net (code "90") (name "unconnected-(U1-D7-Pad17)") (class "Default")
      (node (ref "U1") (pin "17") (pinfunction "D7_17") (pintype "bidirectional"))
    )
    (net (code "91") (name "unconnected-(U1-D8-Pad19)") (class "Default")
      (node (ref "U1") (pin "19") (pinfunction "D8_19") (pintype "bidirectional"))
    )
    (net (code "92") (name "unconnected-(U1-DOUT-Pad22)") (class "Default")
      (node (ref "U1") (pin "22") (pinfunction "DOUT_22") (pintype "output"))
    )
  )
)
